# eCog111_16ch_PWM_Servo.net
KiCad netlist of a schematic drawn in EAGLE
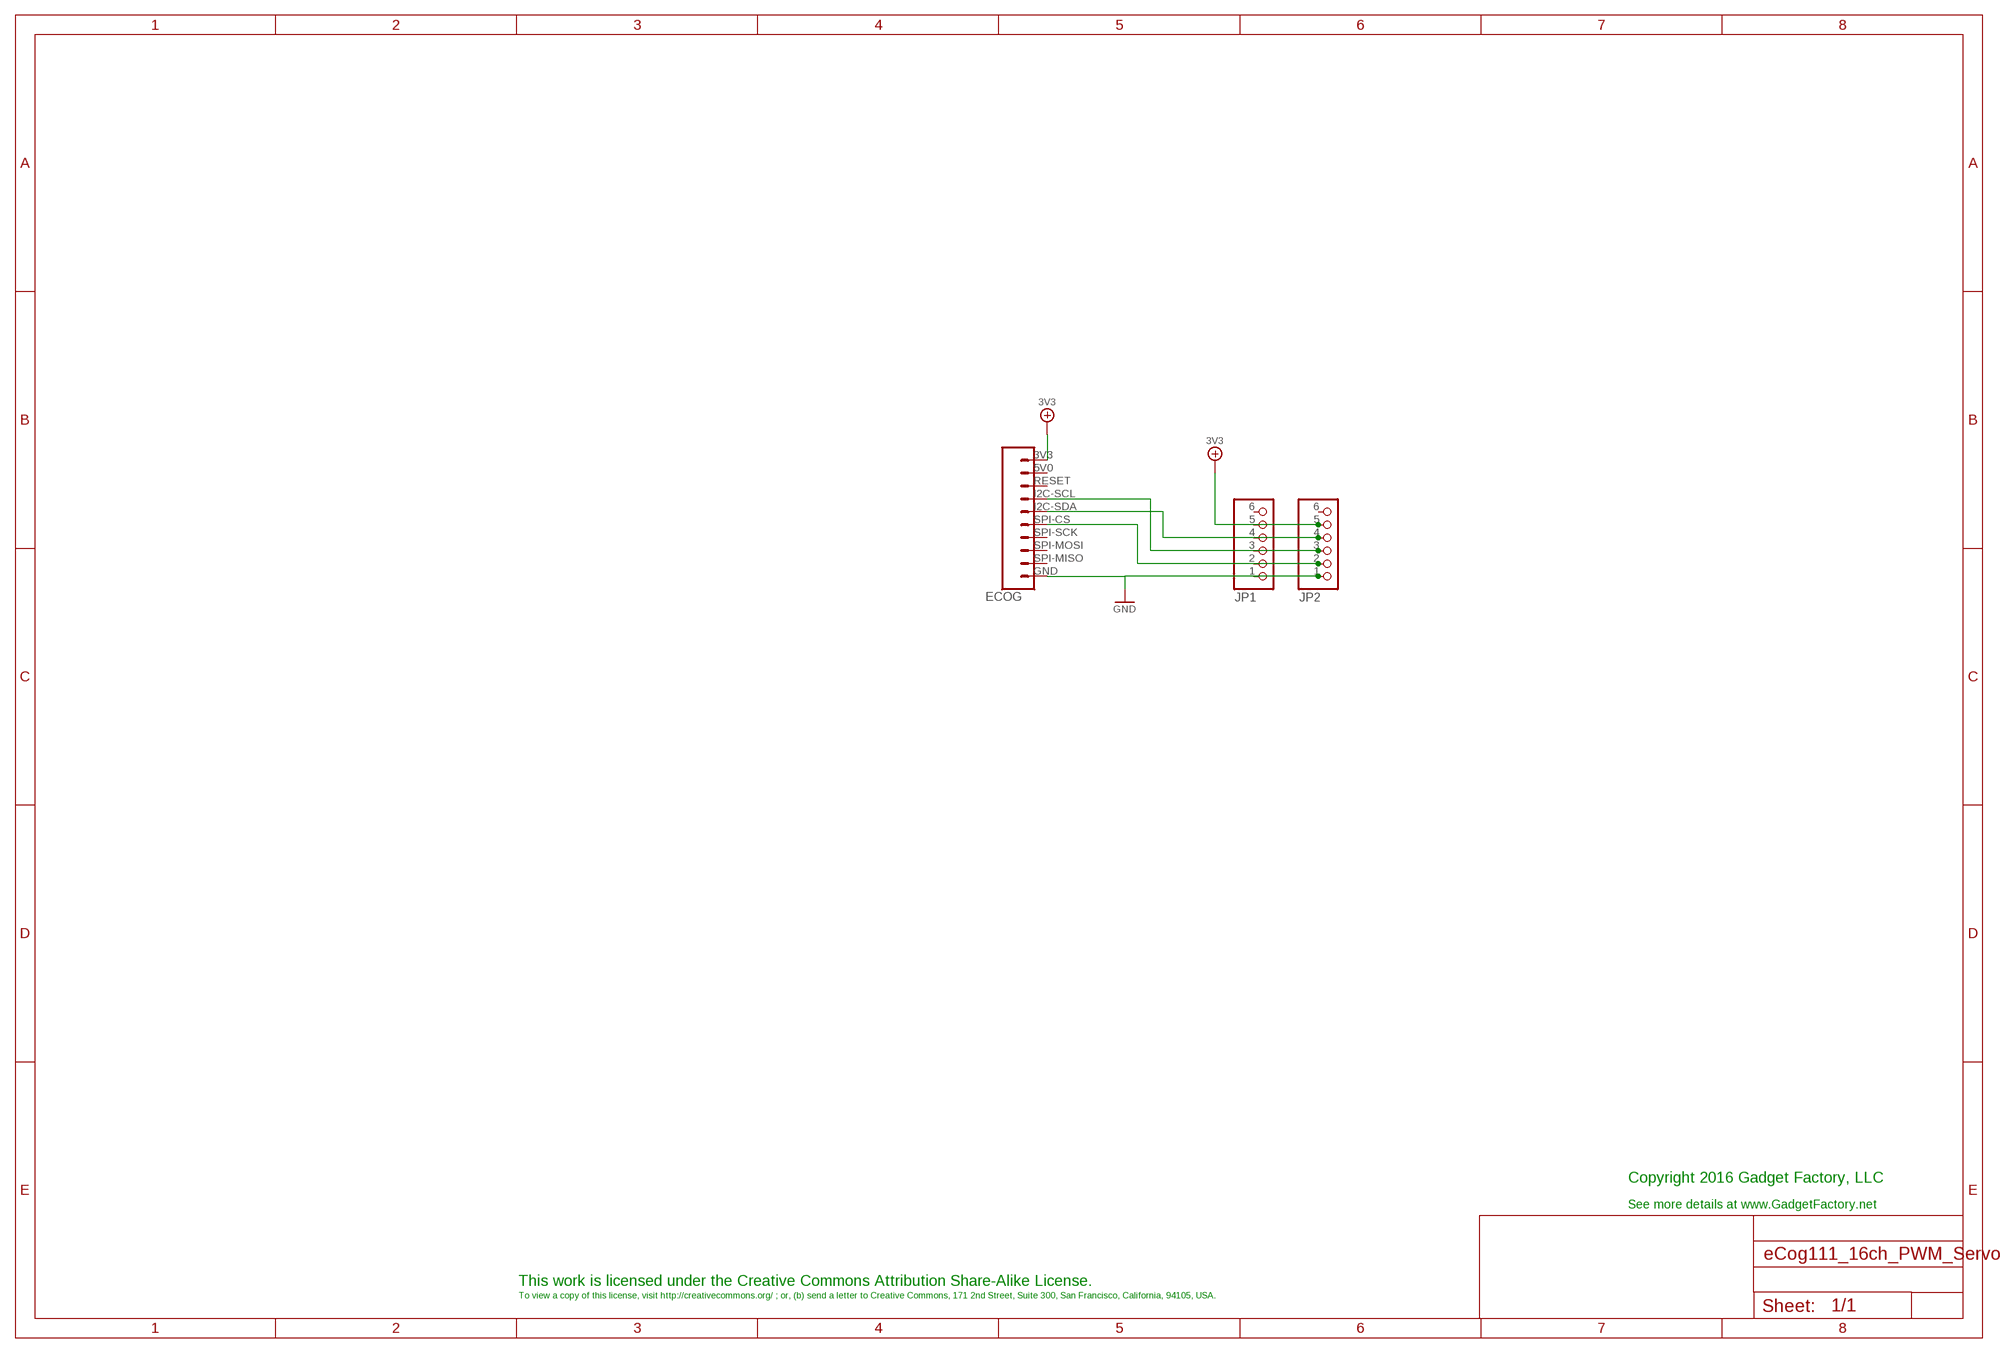
[diagram p0: schematic, sheet 1]

(export (version "E")
  (design (tool "Eeschema 10.0.6"))
  (components
    (comp (ref "ECOG")
      (value "ECOG_BUSES_ROWECOG_BUSES_SMD")
      (footprint "eagle-import:ECOG_BUSES_SMD")
      (libsource (lib "eagle-import") (part "ECOG_BUSES_ROWECOG_BUSES_SMD"))
    )
    (comp (ref "JP1")
      (value "PINHD-1X6")
      (footprint "eagle-import:1X06")
      (libsource (lib "eagle-import") (part "PINHD-1X6"))
    )
    (comp (ref "JP2")
      (value "PINHD-1X6")
      (footprint "eagle-import:1X06")
      (libsource (lib "eagle-import") (part "PINHD-1X6"))
    )
  )
  (nets
    (net (code "1") (name "3V3") (class "Default")
      (node (ref "ECOG") (pin "3V3") (pinfunction "3V3_3V3") (pintype "passive"))
      (node (ref "JP1") (pin "5") (pinfunction "5_5") (pintype "passive"))
      (node (ref "JP2") (pin "5") (pinfunction "5_5") (pintype "passive"))
    )
    (net (code "2") (name "GND") (class "Default")
      (node (ref "ECOG") (pin "GND") (pinfunction "GND_GND") (pintype "passive"))
      (node (ref "JP1") (pin "1") (pinfunction "1_1") (pintype "passive"))
      (node (ref "JP2") (pin "1") (pinfunction "1_1") (pintype "passive"))
    )
    (net (code "3") (name "Net-(ECOG-PadI2C-SCL)") (class "Default")
      (node (ref "ECOG") (pin "I2C-SCL") (pinfunction "I2C-SCL_I2C-SCL") (pintype "passive"))
      (node (ref "JP1") (pin "3") (pinfunction "3_3") (pintype "passive"))
      (node (ref "JP2") (pin "3") (pinfunction "3_3") (pintype "passive"))
    )
    (net (code "4") (name "Net-(ECOG-PadI2C-SDA)") (class "Default")
      (node (ref "ECOG") (pin "I2C-SDA") (pinfunction "I2C-SDA_I2C-SDA") (pintype "passive"))
      (node (ref "JP1") (pin "4") (pinfunction "4_4") (pintype "passive"))
      (node (ref "JP2") (pin "4") (pinfunction "4_4") (pintype "passive"))
    )
    (net (code "5") (name "Net-(ECOG-PadSPI-CS)") (class "Default")
      (node (ref "ECOG") (pin "SPI-CS") (pinfunction "SPI-CS_SPI-CS") (pintype "passive"))
      (node (ref "JP1") (pin "2") (pinfunction "2_2") (pintype "passive"))
      (node (ref "JP2") (pin "2") (pinfunction "2_2") (pintype "passive"))
    )
    (net (code "6") (name "unconnected-(ECOG-Pad5V0)") (class "Default")
      (node (ref "ECOG") (pin "5V0") (pinfunction "5V0_5V0") (pintype "passive"))
    )
    (net (code "7") (name "unconnected-(ECOG-PadRESET)") (class "Default")
      (node (ref "ECOG") (pin "RESET") (pinfunction "RESET_RESET") (pintype "passive"))
    )
    (net (code "8") (name "unconnected-(ECOG-PadSPI-MISO)") (class "Default")
      (node (ref "ECOG") (pin "SPI-MISO") (pinfunction "SPI-MISO_SPI-MISO") (pintype "passive"))
    )
    (net (code "9") (name "unconnected-(ECOG-PadSPI-MOSI)") (class "Default")
      (node (ref "ECOG") (pin "SPI-MOSI") (pinfunction "SPI-MOSI_SPI-MOSI") (pintype "passive"))
    )
    (net (code "10") (name "unconnected-(ECOG-PadSPI-SCK)") (class "Default")
      (node (ref "ECOG") (pin "SPI-SCK") (pinfunction "SPI-SCK_SPI-SCK") (pintype "passive"))
    )
    (net (code "11") (name "unconnected-(JP1-Pad6)") (class "Default")
      (node (ref "JP1") (pin "6") (pinfunction "6_6") (pintype "passive"))
    )
    (net (code "12") (name "unconnected-(JP2-Pad6)") (class "Default")
      (node (ref "JP2") (pin "6") (pinfunction "6_6") (pintype "passive"))
    )
  )
)
